# bt_lokomotivy_v1.net
KiCad netlist of a schematic drawn in EAGLE
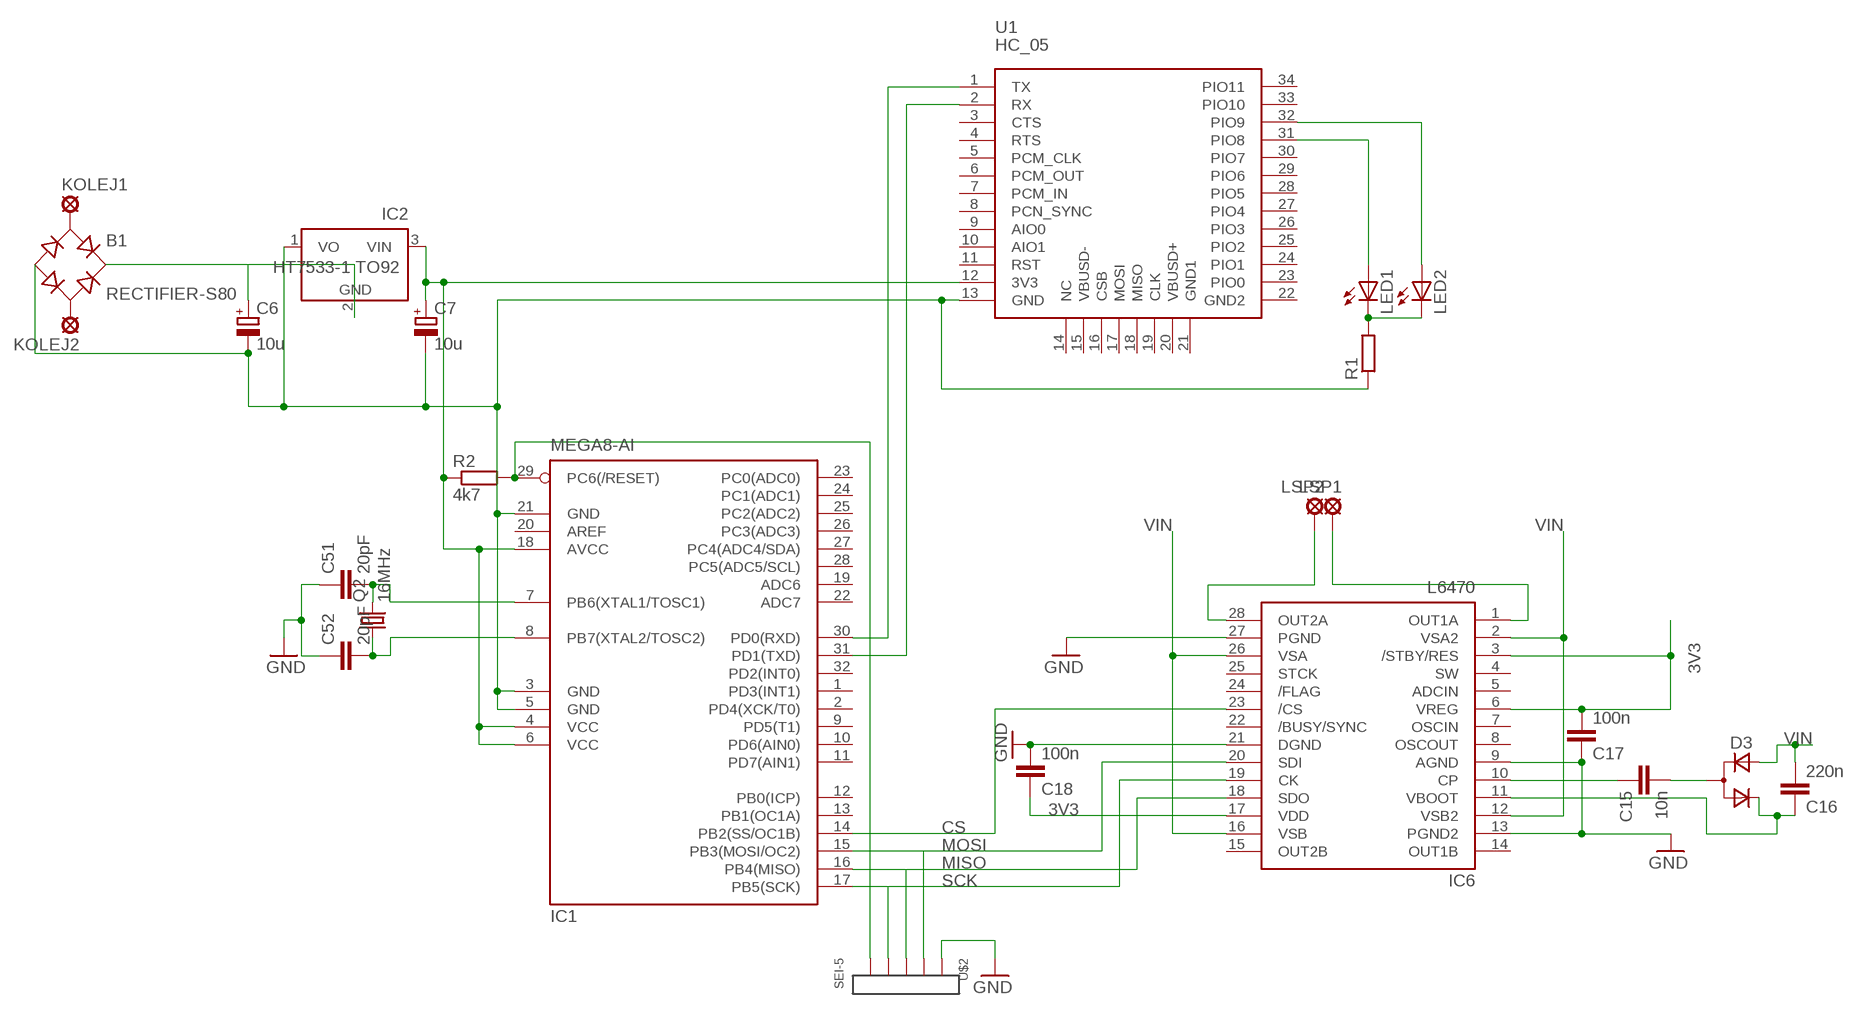
[diagram p0: schematic, sheet 1]

(export (version "E")
  (design (tool "Eeschema 10.0.6"))
  (components
    (comp (ref "B1")
      (value "RECTIFIER-S80")
      (footprint "eagle-import:TO-269AA")
      (libsource (lib "eagle-import") (part "RECTIFIER-S80"))
    )
    (comp (ref "C6")
      (value "10u")
      (footprint "eagle-import:153CLV-0405")
      (libsource (lib "eagle-import") (part "CPOL-EU153CLV-0405"))
    )
    (comp (ref "C7")
      (value "10u")
      (footprint "eagle-import:153CLV-0405")
      (libsource (lib "eagle-import") (part "CPOL-EU153CLV-0405"))
    )
    (comp (ref "C15")
      (value "10n")
      (footprint "eagle-import:C0603")
      (libsource (lib "eagle-import") (part "resistor_C-EUC0603"))
    )
    (comp (ref "C16")
      (value "220n")
      (footprint "eagle-import:C0603K")
      (libsource (lib "eagle-import") (part "resistor_C-EUC0603K"))
    )
    (comp (ref "C17")
      (value "100n")
      (footprint "eagle-import:C0402")
      (libsource (lib "eagle-import") (part "resistor_C-EUC0402"))
    )
    (comp (ref "C18")
      (value "100n")
      (footprint "eagle-import:C0402")
      (libsource (lib "eagle-import") (part "resistor_C-EUC0402"))
    )
    (comp (ref "C51")
      (value "20pF")
      (footprint "eagle-import:C0603")
      (libsource (lib "eagle-import") (part "C-EUC0603"))
    )
    (comp (ref "C52")
      (value "20pF")
      (footprint "eagle-import:C0603")
      (libsource (lib "eagle-import") (part "C-EUC0603"))
    )
    (comp (ref "D3")
      (value "D_ACACSOT323")
      (footprint "eagle-import:SOT323")
      (libsource (lib "eagle-import") (part "D_ACACSOT323"))
    )
    (comp (ref "IC1")
      (value "MEGA8-AI")
      (footprint "eagle-import:TQFP32-08")
      (fields (field (name "MPN") "ATMEGA8-16AU"))
      (libsource (lib "eagle-import") (part "MEGA8-AI"))
    )
    (comp (ref "IC2")
      (value "HT7533-1 TO92")
      (footprint "eagle-import:TO92")
      (fields (field (name "MF") "NATIONAL SEMICONDUCTOR") (field (name "MPN") "LM2936Z-3.0/NOPB"))
      (libsource (lib "eagle-import") (part "LM2936?Z-3.0"))
    )
    (comp (ref "IC6")
      (value "L6470")
      (footprint "eagle-import:HTSSOP28")
      (libsource (lib "eagle-import") (part "L6470"))
    )
    (comp (ref "KOLEJ1")
      (value "LSP10")
      (footprint "eagle-import:LSP10")
      (libsource (lib "eagle-import") (part "LSP10"))
    )
    (comp (ref "KOLEJ2")
      (value "LSP10")
      (footprint "eagle-import:LSP10")
      (libsource (lib "eagle-import") (part "LSP10"))
    )
    (comp (ref "LED1")
      (value "LEDCHIPLED_0603")
      (footprint "eagle-import:CHIPLED_0603")
      (libsource (lib "eagle-import") (part "LEDCHIPLED_0603"))
    )
    (comp (ref "LED2")
      (value "LEDCHIPLED_0603")
      (footprint "eagle-import:CHIPLED_0603")
      (libsource (lib "eagle-import") (part "LEDCHIPLED_0603"))
    )
    (comp (ref "LSP1")
      (value "LSP10")
      (footprint "eagle-import:LSP10")
      (libsource (lib "eagle-import") (part "LSP10"))
    )
    (comp (ref "LSP2")
      (value "LSP10")
      (footprint "eagle-import:LSP10")
      (libsource (lib "eagle-import") (part "LSP10"))
    )
    (comp (ref "Q2")
      (value "16MHz")
      (footprint "eagle-import:HC49UP")
      (libsource (lib "eagle-import") (part "CRYSTALHC49UP"))
    )
    (comp (ref "R1")
      (value "R-EU_R0603")
      (footprint "eagle-import:R0603")
      (libsource (lib "eagle-import") (part "R-EU_R0603"))
    )
    (comp (ref "R2")
      (value "4k7")
      (footprint "eagle-import:R0603")
      (libsource (lib "eagle-import") (part "R-EU_R0603"))
    )
    (comp (ref "U$2")
      (value "SEI-5")
      (footprint "eagle-import:SEI-5")
      (libsource (lib "eagle-import") (part "SEI-5"))
    )
    (comp (ref "U1")
      (value "HC_05")
      (footprint "eagle-import:BLUETOOTH_SMD")
      (libsource (lib "eagle-import") (part "HC_05"))
    )
  )
  (nets
    (net (code "1") (name "/3V3") (class "Default")
      (node (ref "C17") (pin "2") (pinfunction "2_2") (pintype "passive"))
      (node (ref "C18") (pin "1") (pinfunction "1_1") (pintype "passive"))
      (node (ref "C7") (pin "+") (pinfunction "+_+") (pintype "passive"))
      (node (ref "IC1") (pin "18") (pinfunction "AVCC_18") (pintype "power_in"))
      (node (ref "IC1") (pin "4") (pinfunction "VCC_4") (pintype "power_in"))
      (node (ref "IC1") (pin "6") (pinfunction "VCC_6") (pintype "power_in"))
      (node (ref "IC2") (pin "3") (pinfunction "VIN_3") (pintype "input"))
      (node (ref "IC6") (pin "17") (pinfunction "VDD_17") (pintype "power_in"))
      (node (ref "IC6") (pin "3") (pinfunction "/STBY/RES_3") (pintype "input"))
      (node (ref "IC6") (pin "6") (pinfunction "VREG_6") (pintype "power_in"))
      (node (ref "R2") (pin "1") (pinfunction "1_1") (pintype "passive"))
      (node (ref "U1") (pin "12") (pinfunction "3V3_12") (pintype "bidirectional"))
    )
    (net (code "2") (name "/CS") (class "Default")
      (node (ref "IC1") (pin "14") (pinfunction "PB2(SS/OC1B)_14") (pintype "bidirectional"))
      (node (ref "IC6") (pin "23") (pinfunction "/CS_23") (pintype "input"))
    )
    (net (code "3") (name "/MISO") (class "Default")
      (node (ref "IC1") (pin "16") (pinfunction "PB4(MISO)_16") (pintype "bidirectional"))
      (node (ref "IC6") (pin "18") (pinfunction "SDO_18") (pintype "output"))
      (node (ref "U$2") (pin "P$3") (pinfunction "P$3_P$3") (pintype "bidirectional"))
    )
    (net (code "4") (name "/MOSI") (class "Default")
      (node (ref "IC1") (pin "15") (pinfunction "PB3(MOSI/OC2)_15") (pintype "bidirectional"))
      (node (ref "IC6") (pin "20") (pinfunction "SDI_20") (pintype "input"))
      (node (ref "U$2") (pin "P$2") (pinfunction "P$2_P$2") (pintype "bidirectional"))
    )
    (net (code "5") (name "/SCK") (class "Default")
      (node (ref "IC1") (pin "17") (pinfunction "PB5(SCK)_17") (pintype "bidirectional"))
      (node (ref "IC6") (pin "19") (pinfunction "CK_19") (pintype "input"))
      (node (ref "U$2") (pin "P$4") (pinfunction "P$4_P$4") (pintype "bidirectional"))
    )
    (net (code "6") (name "/VIN") (class "Default")
      (node (ref "B1") (pin "+") (pinfunction "+_+") (pintype "passive"))
      (node (ref "C16") (pin "2") (pinfunction "2_2") (pintype "passive"))
      (node (ref "C6") (pin "+") (pinfunction "+_+") (pintype "passive"))
      (node (ref "D3") (pin "3") (pinfunction "A_3") (pintype "passive"))
      (node (ref "IC2") (pin "2") (pinfunction "GND_2") (pintype "passive"))
      (node (ref "IC6") (pin "12") (pinfunction "VSB2_12") (pintype "power_in"))
      (node (ref "IC6") (pin "16") (pinfunction "VSB_16") (pintype "power_in"))
      (node (ref "IC6") (pin "2") (pinfunction "VSA2_2") (pintype "power_in"))
      (node (ref "IC6") (pin "26") (pinfunction "VSA_26") (pintype "power_in"))
    )
    (net (code "7") (name "GND") (class "Default")
      (node (ref "B1") (pin "-") (pinfunction "-_-") (pintype "passive"))
      (node (ref "C17") (pin "1") (pinfunction "1_1") (pintype "passive"))
      (node (ref "C18") (pin "2") (pinfunction "2_2") (pintype "passive"))
      (node (ref "C51") (pin "1") (pinfunction "1_1") (pintype "passive"))
      (node (ref "C52") (pin "1") (pinfunction "1_1") (pintype "passive"))
      (node (ref "C6") (pin "-") (pinfunction "-_-") (pintype "passive"))
      (node (ref "C7") (pin "-") (pinfunction "-_-") (pintype "passive"))
      (node (ref "IC1") (pin "21") (pinfunction "GND_21") (pintype "power_in"))
      (node (ref "IC1") (pin "3") (pinfunction "GND_3") (pintype "power_in"))
      (node (ref "IC1") (pin "5") (pinfunction "GND_5") (pintype "power_in"))
      (node (ref "IC2") (pin "1") (pinfunction "VO_1") (pintype "passive"))
      (node (ref "IC6") (pin "13") (pinfunction "PGND2_13") (pintype "power_in"))
      (node (ref "IC6") (pin "21") (pinfunction "DGND_21") (pintype "power_in"))
      (node (ref "IC6") (pin "27") (pinfunction "PGND_27") (pintype "power_in"))
      (node (ref "IC6") (pin "9") (pinfunction "AGND_9") (pintype "power_in"))
      (node (ref "R1") (pin "1") (pinfunction "1_1") (pintype "passive"))
      (node (ref "U$2") (pin "P$1") (pinfunction "P$1_P$1") (pintype "bidirectional"))
      (node (ref "U1") (pin "13") (pinfunction "GND_13") (pintype "bidirectional"))
    )
    (net (code "8") (name "Net-(B1-PadAC1)") (class "Default")
      (node (ref "B1") (pin "AC1") (pinfunction "AC1_AC1") (pintype "passive"))
      (node (ref "KOLEJ1") (pin "MP") (pinfunction "MP_MP") (pintype "passive"))
    )
    (net (code "9") (name "Net-(B1-PadAC2)") (class "Default")
      (node (ref "B1") (pin "AC2") (pinfunction "AC2_AC2") (pintype "passive"))
      (node (ref "KOLEJ2") (pin "MP") (pinfunction "MP_MP") (pintype "passive"))
    )
    (net (code "10") (name "Net-(D3-C)") (class "Default")
      (node (ref "C16") (pin "1") (pinfunction "1_1") (pintype "passive"))
      (node (ref "D3") (pin "2") (pinfunction "C_2") (pintype "passive"))
      (node (ref "IC6") (pin "11") (pinfunction "VBOOT_11") (pintype "power_in"))
    )
    (net (code "11") (name "Net-(D3-CA)") (class "Default")
      (node (ref "C15") (pin "2") (pinfunction "2_2") (pintype "passive"))
      (node (ref "D3") (pin "1") (pinfunction "CA_1") (pintype "passive"))
    )
    (net (code "12") (name "Net-(IC1-PB6(XTAL1{slash}TOSC1))") (class "Default")
      (node (ref "C51") (pin "2") (pinfunction "2_2") (pintype "passive"))
      (node (ref "IC1") (pin "7") (pinfunction "PB6(XTAL1/TOSC1)_7") (pintype "bidirectional"))
      (node (ref "Q2") (pin "2") (pinfunction "2_2") (pintype "passive"))
    )
    (net (code "13") (name "Net-(IC1-PB7(XTAL2{slash}TOSC2))") (class "Default")
      (node (ref "C52") (pin "2") (pinfunction "2_2") (pintype "passive"))
      (node (ref "IC1") (pin "8") (pinfunction "PB7(XTAL2/TOSC2)_8") (pintype "bidirectional"))
      (node (ref "Q2") (pin "1") (pinfunction "1_1") (pintype "passive"))
    )
    (net (code "14") (name "Net-(IC1-PC6({slash}RESET))") (class "Default")
      (node (ref "IC1") (pin "29") (pinfunction "PC6(/RESET)_29") (pintype "bidirectional"))
      (node (ref "R2") (pin "2") (pinfunction "2_2") (pintype "passive"))
      (node (ref "U$2") (pin "P$5") (pinfunction "P$5_P$5") (pintype "bidirectional"))
    )
    (net (code "15") (name "Net-(IC1-PD0(RXD))") (class "Default")
      (node (ref "IC1") (pin "30") (pinfunction "PD0(RXD)_30") (pintype "bidirectional"))
      (node (ref "U1") (pin "1") (pinfunction "TX_1") (pintype "bidirectional"))
    )
    (net (code "16") (name "Net-(IC1-PD1(TXD))") (class "Default")
      (node (ref "IC1") (pin "31") (pinfunction "PD1(TXD)_31") (pintype "bidirectional"))
      (node (ref "U1") (pin "2") (pinfunction "RX_2") (pintype "bidirectional"))
    )
    (net (code "17") (name "Net-(IC6-CP)") (class "Default")
      (node (ref "C15") (pin "1") (pinfunction "1_1") (pintype "passive"))
      (node (ref "IC6") (pin "10") (pinfunction "CP_10") (pintype "output"))
    )
    (net (code "18") (name "Net-(IC6-OUT1A)") (class "Default")
      (node (ref "IC6") (pin "1") (pinfunction "OUT1A_1") (pintype "output"))
      (node (ref "LSP1") (pin "MP") (pinfunction "MP_MP") (pintype "passive"))
    )
    (net (code "19") (name "Net-(IC6-OUT2A)") (class "Default")
      (node (ref "IC6") (pin "28") (pinfunction "OUT2A_28") (pintype "output"))
      (node (ref "LSP2") (pin "MP") (pinfunction "MP_MP") (pintype "passive"))
    )
    (net (code "20") (name "Net-(LED1-PadC)") (class "Default")
      (node (ref "LED1") (pin "C") (pinfunction "C_C") (pintype "passive"))
      (node (ref "LED2") (pin "C") (pinfunction "C_C") (pintype "passive"))
      (node (ref "R1") (pin "2") (pinfunction "2_2") (pintype "passive"))
    )
    (net (code "21") (name "Net-(U1-PIO8)") (class "Default")
      (node (ref "LED1") (pin "A") (pinfunction "A_A") (pintype "passive"))
      (node (ref "U1") (pin "31") (pinfunction "PIO8_31") (pintype "bidirectional"))
    )
    (net (code "22") (name "Net-(U1-PIO9)") (class "Default")
      (node (ref "LED2") (pin "A") (pinfunction "A_A") (pintype "passive"))
      (node (ref "U1") (pin "32") (pinfunction "PIO9_32") (pintype "bidirectional"))
    )
    (net (code "23") (name "unconnected-(IC1-ADC6-Pad19)") (class "Default")
      (node (ref "IC1") (pin "19") (pinfunction "ADC6_19") (pintype "bidirectional"))
    )
    (net (code "24") (name "unconnected-(IC1-ADC7-Pad22)") (class "Default")
      (node (ref "IC1") (pin "22") (pinfunction "ADC7_22") (pintype "bidirectional"))
    )
    (net (code "25") (name "unconnected-(IC1-AREF-Pad20)") (class "Default")
      (node (ref "IC1") (pin "20") (pinfunction "AREF_20") (pintype "passive"))
    )
    (net (code "26") (name "unconnected-(IC1-PB0(ICP)-Pad12)") (class "Default")
      (node (ref "IC1") (pin "12") (pinfunction "PB0(ICP)_12") (pintype "bidirectional"))
    )
    (net (code "27") (name "unconnected-(IC1-PB1(OC1A)-Pad13)") (class "Default")
      (node (ref "IC1") (pin "13") (pinfunction "PB1(OC1A)_13") (pintype "bidirectional"))
    )
    (net (code "28") (name "unconnected-(IC1-PC0(ADC0)-Pad23)") (class "Default")
      (node (ref "IC1") (pin "23") (pinfunction "PC0(ADC0)_23") (pintype "bidirectional"))
    )
    (net (code "29") (name "unconnected-(IC1-PC1(ADC1)-Pad24)") (class "Default")
      (node (ref "IC1") (pin "24") (pinfunction "PC1(ADC1)_24") (pintype "bidirectional"))
    )
    (net (code "30") (name "unconnected-(IC1-PC2(ADC2)-Pad25)") (class "Default")
      (node (ref "IC1") (pin "25") (pinfunction "PC2(ADC2)_25") (pintype "bidirectional"))
    )
    (net (code "31") (name "unconnected-(IC1-PC3(ADC3)-Pad26)") (class "Default")
      (node (ref "IC1") (pin "26") (pinfunction "PC3(ADC3)_26") (pintype "bidirectional"))
    )
    (net (code "32") (name "unconnected-(IC1-PC4(ADC4{slash}SDA)-Pad27)") (class "Default")
      (node (ref "IC1") (pin "27") (pinfunction "PC4(ADC4/SDA)_27") (pintype "bidirectional"))
    )
    (net (code "33") (name "unconnected-(IC1-PC5(ADC5{slash}SCL)-Pad28)") (class "Default")
      (node (ref "IC1") (pin "28") (pinfunction "PC5(ADC5/SCL)_28") (pintype "bidirectional"))
    )
    (net (code "34") (name "unconnected-(IC1-PD2(INT0)-Pad32)") (class "Default")
      (node (ref "IC1") (pin "32") (pinfunction "PD2(INT0)_32") (pintype "bidirectional"))
    )
    (net (code "35") (name "unconnected-(IC1-PD3(INT1)-Pad1)") (class "Default")
      (node (ref "IC1") (pin "1") (pinfunction "PD3(INT1)_1") (pintype "bidirectional"))
    )
    (net (code "36") (name "unconnected-(IC1-PD4(XCK{slash}T0)-Pad2)") (class "Default")
      (node (ref "IC1") (pin "2") (pinfunction "PD4(XCK/T0)_2") (pintype "bidirectional"))
    )
    (net (code "37") (name "unconnected-(IC1-PD5(T1)-Pad9)") (class "Default")
      (node (ref "IC1") (pin "9") (pinfunction "PD5(T1)_9") (pintype "bidirectional"))
    )
    (net (code "38") (name "unconnected-(IC1-PD6(AIN0)-Pad10)") (class "Default")
      (node (ref "IC1") (pin "10") (pinfunction "PD6(AIN0)_10") (pintype "bidirectional"))
    )
    (net (code "39") (name "unconnected-(IC1-PD7(AIN1)-Pad11)") (class "Default")
      (node (ref "IC1") (pin "11") (pinfunction "PD7(AIN1)_11") (pintype "bidirectional"))
    )
    (net (code "40") (name "unconnected-(IC6-ADCIN-Pad5)") (class "Default")
      (node (ref "IC6") (pin "5") (pinfunction "ADCIN_5") (pintype "input"))
    )
    (net (code "41") (name "unconnected-(IC6-OSCIN-Pad7)") (class "Default")
      (node (ref "IC6") (pin "7") (pinfunction "OSCIN_7") (pintype "input"))
    )
    (net (code "42") (name "unconnected-(IC6-OSCOUT-Pad8)") (class "Default")
      (node (ref "IC6") (pin "8") (pinfunction "OSCOUT_8") (pintype "output"))
    )
    (net (code "43") (name "unconnected-(IC6-OUT1B-Pad14)") (class "Default")
      (node (ref "IC6") (pin "14") (pinfunction "OUT1B_14") (pintype "output"))
    )
    (net (code "44") (name "unconnected-(IC6-OUT2B-Pad15)") (class "Default")
      (node (ref "IC6") (pin "15") (pinfunction "OUT2B_15") (pintype "output"))
    )
    (net (code "45") (name "unconnected-(IC6-STCK-Pad25)") (class "Default")
      (node (ref "IC6") (pin "25") (pinfunction "STCK_25") (pintype "input"))
    )
    (net (code "46") (name "unconnected-(IC6-SW-Pad4)") (class "Default")
      (node (ref "IC6") (pin "4") (pinfunction "SW_4") (pintype "input"))
    )
    (net (code "47") (name "unconnected-(IC6-{slash}BUSY{slash}SYNC-Pad22)") (class "Default")
      (node (ref "IC6") (pin "22") (pinfunction "/BUSY/SYNC_22") (pintype "output"))
    )
    (net (code "48") (name "unconnected-(IC6-{slash}FLAG-Pad24)") (class "Default")
      (node (ref "IC6") (pin "24") (pinfunction "/FLAG_24") (pintype "output"))
    )
    (net (code "49") (name "unconnected-(U1-AIO0-Pad9)") (class "Default")
      (node (ref "U1") (pin "9") (pinfunction "AIO0_9") (pintype "bidirectional"))
    )
    (net (code "50") (name "unconnected-(U1-AIO1-Pad10)") (class "Default")
      (node (ref "U1") (pin "10") (pinfunction "AIO1_10") (pintype "bidirectional"))
    )
    (net (code "51") (name "unconnected-(U1-CLK-Pad19)") (class "Default")
      (node (ref "U1") (pin "19") (pinfunction "CLK_19") (pintype "bidirectional"))
    )
    (net (code "52") (name "unconnected-(U1-CSB-Pad16)") (class "Default")
      (node (ref "U1") (pin "16") (pinfunction "CSB_16") (pintype "bidirectional"))
    )
    (net (code "53") (name "unconnected-(U1-CTS-Pad3)") (class "Default")
      (node (ref "U1") (pin "3") (pinfunction "CTS_3") (pintype "bidirectional"))
    )
    (net (code "54") (name "unconnected-(U1-GND1-Pad21)") (class "Default")
      (node (ref "U1") (pin "21") (pinfunction "GND1_21") (pintype "bidirectional"))
    )
    (net (code "55") (name "unconnected-(U1-GND2-Pad22)") (class "Default")
      (node (ref "U1") (pin "22") (pinfunction "GND2_22") (pintype "bidirectional"))
    )
    (net (code "56") (name "unconnected-(U1-MISO-Pad18)") (class "Default")
      (node (ref "U1") (pin "18") (pinfunction "MISO_18") (pintype "bidirectional"))
    )
    (net (code "57") (name "unconnected-(U1-MOSI-Pad17)") (class "Default")
      (node (ref "U1") (pin "17") (pinfunction "MOSI_17") (pintype "bidirectional"))
    )
    (net (code "58") (name "unconnected-(U1-NC-Pad14)") (class "Default")
      (node (ref "U1") (pin "14") (pinfunction "NC_14") (pintype "bidirectional"))
    )
    (net (code "59") (name "unconnected-(U1-PCM_CLK-Pad5)") (class "Default")
      (node (ref "U1") (pin "5") (pinfunction "PCM_CLK_5") (pintype "bidirectional"))
    )
    (net (code "60") (name "unconnected-(U1-PCM_IN-Pad7)") (class "Default")
      (node (ref "U1") (pin "7") (pinfunction "PCM_IN_7") (pintype "bidirectional"))
    )
    (net (code "61") (name "unconnected-(U1-PCM_OUT-Pad6)") (class "Default")
      (node (ref "U1") (pin "6") (pinfunction "PCM_OUT_6") (pintype "bidirectional"))
    )
    (net (code "62") (name "unconnected-(U1-PCN_SYNC-Pad8)") (class "Default")
      (node (ref "U1") (pin "8") (pinfunction "PCN_SYNC_8") (pintype "bidirectional"))
    )
    (net (code "63") (name "unconnected-(U1-PIO0-Pad23)") (class "Default")
      (node (ref "U1") (pin "23") (pinfunction "PIO0_23") (pintype "bidirectional"))
    )
    (net (code "64") (name "unconnected-(U1-PIO1-Pad24)") (class "Default")
      (node (ref "U1") (pin "24") (pinfunction "PIO1_24") (pintype "bidirectional"))
    )
    (net (code "65") (name "unconnected-(U1-PIO2-Pad25)") (class "Default")
      (node (ref "U1") (pin "25") (pinfunction "PIO2_25") (pintype "bidirectional"))
    )
    (net (code "66") (name "unconnected-(U1-PIO3-Pad26)") (class "Default")
      (node (ref "U1") (pin "26") (pinfunction "PIO3_26") (pintype "bidirectional"))
    )
    (net (code "67") (name "unconnected-(U1-PIO4-Pad27)") (class "Default")
      (node (ref "U1") (pin "27") (pinfunction "PIO4_27") (pintype "bidirectional"))
    )
    (net (code "68") (name "unconnected-(U1-PIO5-Pad28)") (class "Default")
      (node (ref "U1") (pin "28") (pinfunction "PIO5_28") (pintype "bidirectional"))
    )
    (net (code "69") (name "unconnected-(U1-PIO6-Pad29)") (class "Default")
      (node (ref "U1") (pin "29") (pinfunction "PIO6_29") (pintype "bidirectional"))
    )
    (net (code "70") (name "unconnected-(U1-PIO7-Pad30)") (class "Default")
      (node (ref "U1") (pin "30") (pinfunction "PIO7_30") (pintype "bidirectional"))
    )
    (net (code "71") (name "unconnected-(U1-PIO10-Pad33)") (class "Default")
      (node (ref "U1") (pin "33") (pinfunction "PIO10_33") (pintype "bidirectional"))
    )
    (net (code "72") (name "unconnected-(U1-PIO11-Pad34)") (class "Default")
      (node (ref "U1") (pin "34") (pinfunction "PIO11_34") (pintype "bidirectional"))
    )
    (net (code "73") (name "unconnected-(U1-RST-Pad11)") (class "Default")
      (node (ref "U1") (pin "11") (pinfunction "RST_11") (pintype "bidirectional"))
    )
    (net (code "74") (name "unconnected-(U1-RTS-Pad4)") (class "Default")
      (node (ref "U1") (pin "4") (pinfunction "RTS_4") (pintype "bidirectional"))
    )
    (net (code "75") (name "unconnected-(U1-VBUSD+-Pad20)") (class "Default")
      (node (ref "U1") (pin "20") (pinfunction "VBUSD+_20") (pintype "bidirectional"))
    )
    (net (code "76") (name "unconnected-(U1-VBUSD--Pad15)") (class "Default")
      (node (ref "U1") (pin "15") (pinfunction "VBUSD-_15") (pintype "bidirectional"))
    )
  )
)
